# Main.net
KiCad netlist of a schematic drawn in Altium Designer
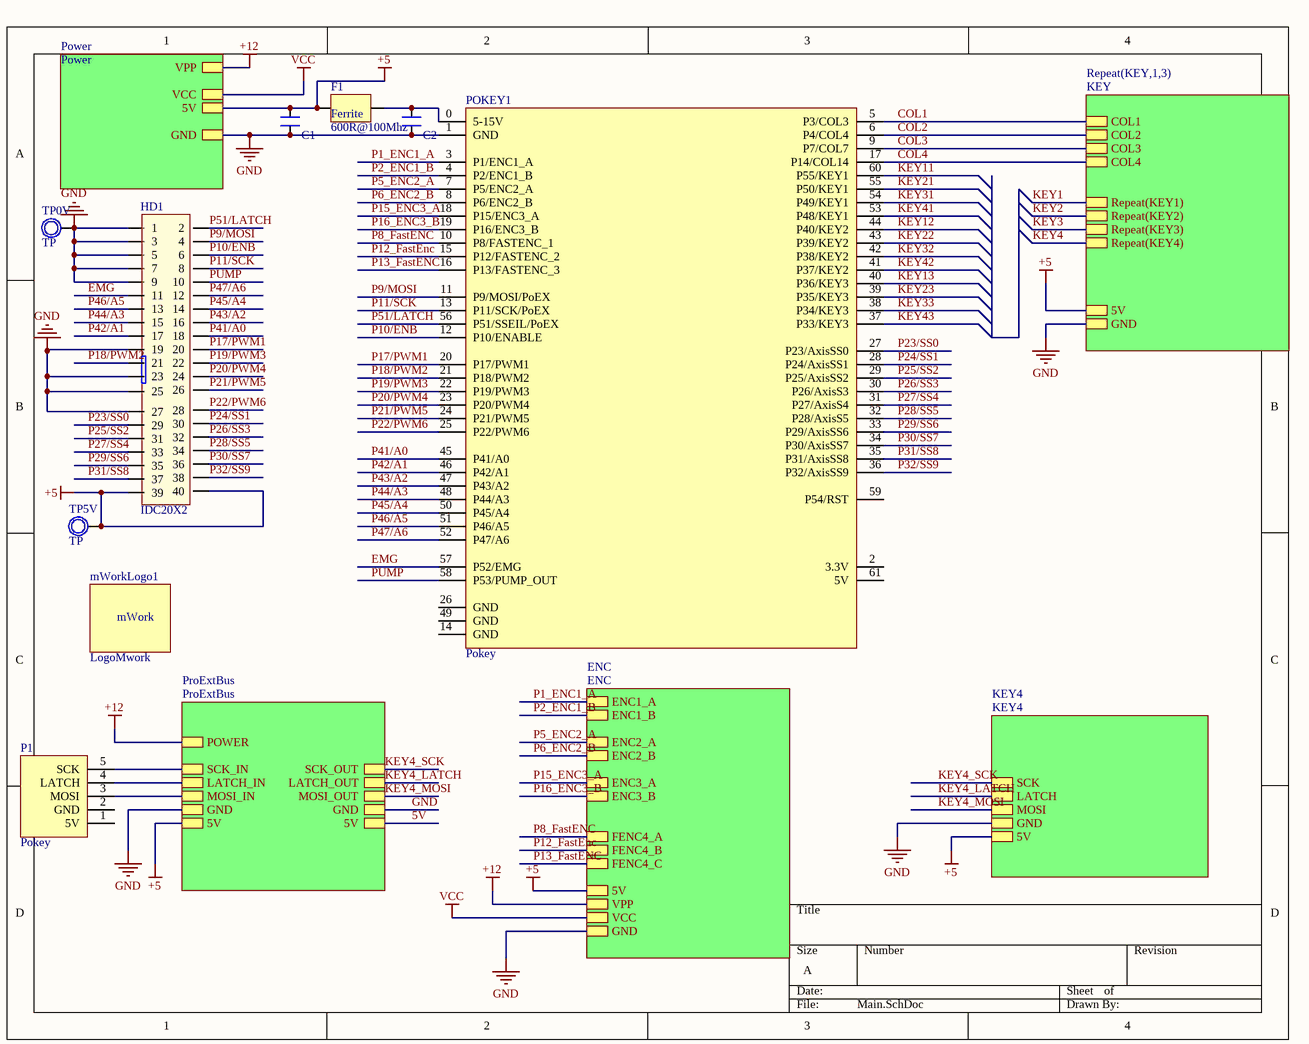
[diagram p0: Main.SchDoc]

(export (version "E")
  (design (tool "Eeschema 10.0.6"))
  (components
    (comp (ref "C1") (value "CN") (footprint "CN-SMD-0603_big") (libsource (lib "nhan") (part "CN")))
    (comp (ref "C2") (value "CN") (footprint "CN-SMD-0603_big") (libsource (lib "nhan") (part "CN")))
    (comp (ref "F1")
      (value "600R@100Mhz")
      (footprint "Capacitor_805")
      (libsource (lib "nhan") (part "Ferrite"))
    )
    (comp (ref "HD1")
      (value "IDC20X2")
      (footprint "IDC40")
      (description "IDC 13x2")
      (libsource (lib "nhan") (part "IDC20X2"))
    )
    (comp (ref "mWorkLogo1")
      (value "LogoMwork")
      (footprint "LogoMwork30*12")
      (libsource (lib "nhan") (part "LogoMwork"))
    )
    (comp (ref "P1") (value "Pokey") (footprint "JACK5") (libsource (lib "nhan") (part "Pokey_Jack")))
    (comp (ref "POKEY1") (value "Pokey") (footprint "POKEY") (libsource (lib "nhan") (part "Pokey")))
    (comp (ref "TP0V")
      (value "TP")
      (footprint "TP1")
      (description "Test Point")
      (libsource (lib "syhaunguyen") (part "TP1"))
    )
    (comp (ref "TP5V")
      (value "TP")
      (footprint "TP1")
      (description "Test Point")
      (libsource (lib "syhaunguyen") (part "TP1"))
    )
  )
  (nets
    (net (code "1") (name "+5") (class "Default")
      (node (ref "C1") (pin "2") (pinfunction "2_2") (pintype "passive"))
      (node (ref "F1") (pin "1") (pinfunction "1_1") (pintype "passive"))
      (node (ref "HD1") (pin "39") (pinfunction "39_39") (pintype "passive"))
      (node (ref "HD1") (pin "40") (pinfunction "40_40") (pintype "passive"))
      (node (ref "TP5V") (pin "1") (pinfunction "1_1") (pintype "passive"))
    )
    (net (code "4") (name "/COL1") (class "Default")
      (node (ref "POKEY1") (pin "5") (pinfunction "P3/COL3_5") (pintype "passive"))
    )
    (net (code "5") (name "/COL2") (class "Default")
      (node (ref "POKEY1") (pin "6") (pinfunction "P4/COL4_6") (pintype "passive"))
    )
    (net (code "6") (name "/COL3") (class "Default")
      (node (ref "POKEY1") (pin "9") (pinfunction "P7/COL7_9") (pintype "passive"))
    )
    (net (code "7") (name "/COL4") (class "Default")
      (node (ref "POKEY1") (pin "17") (pinfunction "P14/COL14_17") (pintype "passive"))
    )
    (net (code "8") (name "/EMG") (class "Default")
      (node (ref "HD1") (pin "11") (pinfunction "11_11") (pintype "passive"))
      (node (ref "POKEY1") (pin "57") (pinfunction "P52/EMG_57") (pintype "passive"))
    )
    (net (code "16") (name "/KEY11") (class "Default")
      (node (ref "POKEY1") (pin "60") (pinfunction "P55/KEY1_60") (pintype "passive"))
    )
    (net (code "17") (name "/KEY12") (class "Default")
      (node (ref "POKEY1") (pin "44") (pinfunction "P40/KEY2_44") (pintype "passive"))
    )
    (net (code "18") (name "/KEY13") (class "Default")
      (node (ref "POKEY1") (pin "40") (pinfunction "P36/KEY3_40") (pintype "passive"))
    )
    (net (code "19") (name "/KEY21") (class "Default")
      (node (ref "POKEY1") (pin "55") (pinfunction "P50/KEY1_55") (pintype "passive"))
    )
    (net (code "20") (name "/KEY22") (class "Default")
      (node (ref "POKEY1") (pin "43") (pinfunction "P39/KEY2_43") (pintype "passive"))
    )
    (net (code "21") (name "/KEY23") (class "Default")
      (node (ref "POKEY1") (pin "39") (pinfunction "P35/KEY3_39") (pintype "passive"))
    )
    (net (code "22") (name "/KEY31") (class "Default")
      (node (ref "POKEY1") (pin "54") (pinfunction "P49/KEY1_54") (pintype "passive"))
    )
    (net (code "23") (name "/KEY32") (class "Default")
      (node (ref "POKEY1") (pin "42") (pinfunction "P38/KEY2_42") (pintype "passive"))
    )
    (net (code "24") (name "/KEY33") (class "Default")
      (node (ref "POKEY1") (pin "38") (pinfunction "P34/KEY3_38") (pintype "passive"))
    )
    (net (code "25") (name "/KEY41") (class "Default")
      (node (ref "POKEY1") (pin "53") (pinfunction "P48/KEY1_53") (pintype "passive"))
    )
    (net (code "26") (name "/KEY42") (class "Default")
      (node (ref "POKEY1") (pin "41") (pinfunction "P37/KEY2_41") (pintype "passive"))
    )
    (net (code "27") (name "/KEY43") (class "Default")
      (node (ref "POKEY1") (pin "37") (pinfunction "P33/KEY3_37") (pintype "passive"))
    )
    (net (code "28") (name "/LATCH_IN") (class "Default")
      (node (ref "P1") (pin "4") (pinfunction "LATCH_4") (pintype "passive"))
    )
    (net (code "29") (name "/MOSI_IN") (class "Default")
      (node (ref "P1") (pin "3") (pinfunction "MOSI_3") (pintype "passive"))
    )
    (net (code "30") (name "/P1_ENC1_A") (class "Default")
      (node (ref "POKEY1") (pin "3") (pinfunction "P1/ENC1_A_3") (pintype "passive"))
    )
    (net (code "31") (name "/P2_ENC1_B") (class "Default")
      (node (ref "POKEY1") (pin "4") (pinfunction "P2/ENC1_B_4") (pintype "passive"))
    )
    (net (code "32") (name "/P5_ENC2_A") (class "Default")
      (node (ref "POKEY1") (pin "7") (pinfunction "P5/ENC2_A_7") (pintype "passive"))
    )
    (net (code "33") (name "/P6_ENC2_B") (class "Default")
      (node (ref "POKEY1") (pin "8") (pinfunction "P6/ENC2_B_8") (pintype "passive"))
    )
    (net (code "34") (name "/P8_FastENC") (class "Default")
      (node (ref "POKEY1") (pin "10") (pinfunction "P8/FASTENC_1_10") (pintype "passive"))
    )
    (net (code "35") (name "/P9{slash}MOSI") (class "Default")
      (node (ref "HD1") (pin "4") (pinfunction "4_4") (pintype "passive"))
      (node (ref "POKEY1") (pin "11") (pinfunction "P9/MOSI/PoEX_11") (pintype "passive"))
    )
    (net (code "36") (name "/P10{slash}ENB") (class "Default")
      (node (ref "HD1") (pin "6") (pinfunction "6_6") (pintype "passive"))
      (node (ref "POKEY1") (pin "12") (pinfunction "P10/ENABLE_12") (pintype "passive"))
    )
    (net (code "37") (name "/P11{slash}SCK") (class "Default")
      (node (ref "HD1") (pin "8") (pinfunction "8_8") (pintype "passive"))
      (node (ref "POKEY1") (pin "13") (pinfunction "P11/SCK/PoEX_13") (pintype "passive"))
    )
    (net (code "38") (name "/P12_FastEnc") (class "Default")
      (node (ref "POKEY1") (pin "15") (pinfunction "P12/FASTENC_2_15") (pintype "passive"))
    )
    (net (code "39") (name "/P13_FastENC") (class "Default")
      (node (ref "POKEY1") (pin "16") (pinfunction "P13/FASTENC_3_16") (pintype "passive"))
    )
    (net (code "40") (name "/P15_ENC3_A") (class "Default")
      (node (ref "POKEY1") (pin "18") (pinfunction "P15/ENC3_A_18") (pintype "passive"))
    )
    (net (code "41") (name "/P16_ENC3_B") (class "Default")
      (node (ref "POKEY1") (pin "19") (pinfunction "P16/ENC3_B_19") (pintype "passive"))
    )
    (net (code "42") (name "/P17{slash}PWM1") (class "Default")
      (node (ref "HD1") (pin "20") (pinfunction "20_20") (pintype "passive"))
      (node (ref "POKEY1") (pin "20") (pinfunction "P17/PWM1_20") (pintype "passive"))
    )
    (net (code "43") (name "/P18{slash}PWM2") (class "Default")
      (node (ref "HD1") (pin "21") (pinfunction "21_21") (pintype "passive"))
      (node (ref "POKEY1") (pin "21") (pinfunction "P18/PWM2_21") (pintype "passive"))
    )
    (net (code "44") (name "/P19{slash}PWM3") (class "Default")
      (node (ref "HD1") (pin "22") (pinfunction "22_22") (pintype "passive"))
      (node (ref "POKEY1") (pin "22") (pinfunction "P19/PWM3_22") (pintype "passive"))
    )
    (net (code "45") (name "/P20{slash}PWM4") (class "Default")
      (node (ref "HD1") (pin "24") (pinfunction "24_24") (pintype "passive"))
      (node (ref "POKEY1") (pin "23") (pinfunction "P20/PWM4_23") (pintype "passive"))
    )
    (net (code "46") (name "/P21{slash}PWM5") (class "Default")
      (node (ref "HD1") (pin "26") (pinfunction "26_26") (pintype "passive"))
      (node (ref "POKEY1") (pin "24") (pinfunction "P21/PWM5_24") (pintype "passive"))
    )
    (net (code "47") (name "/P22{slash}PWM6") (class "Default")
      (node (ref "HD1") (pin "28") (pinfunction "28_28") (pintype "passive"))
      (node (ref "POKEY1") (pin "25") (pinfunction "P22/PWM6_25") (pintype "passive"))
    )
    (net (code "48") (name "/P23{slash}SS0") (class "Default")
      (node (ref "HD1") (pin "29") (pinfunction "29_29") (pintype "passive"))
      (node (ref "POKEY1") (pin "27") (pinfunction "P23/AxisSS0_27") (pintype "passive"))
    )
    (net (code "49") (name "/P24{slash}SS1") (class "Default")
      (node (ref "HD1") (pin "30") (pinfunction "30_30") (pintype "passive"))
      (node (ref "POKEY1") (pin "28") (pinfunction "P24/AxisSS1_28") (pintype "passive"))
    )
    (net (code "50") (name "/P25{slash}SS2") (class "Default")
      (node (ref "HD1") (pin "31") (pinfunction "31_31") (pintype "passive"))
      (node (ref "POKEY1") (pin "29") (pinfunction "P25/AxisSS2_29") (pintype "passive"))
    )
    (net (code "51") (name "/P26{slash}SS3") (class "Default")
      (node (ref "HD1") (pin "32") (pinfunction "32_32") (pintype "passive"))
      (node (ref "POKEY1") (pin "30") (pinfunction "P26/AxisS3_30") (pintype "passive"))
    )
    (net (code "52") (name "/P27{slash}SS4") (class "Default")
      (node (ref "HD1") (pin "33") (pinfunction "33_33") (pintype "passive"))
      (node (ref "POKEY1") (pin "31") (pinfunction "P27/AxisS4_31") (pintype "passive"))
    )
    (net (code "53") (name "/P28{slash}SS5") (class "Default")
      (node (ref "HD1") (pin "34") (pinfunction "34_34") (pintype "passive"))
      (node (ref "POKEY1") (pin "32") (pinfunction "P28/AxisS5_32") (pintype "passive"))
    )
    (net (code "54") (name "/P29{slash}SS6") (class "Default")
      (node (ref "HD1") (pin "35") (pinfunction "35_35") (pintype "passive"))
      (node (ref "POKEY1") (pin "33") (pinfunction "P29/AxisSS6_33") (pintype "passive"))
    )
    (net (code "55") (name "/P30{slash}SS7") (class "Default")
      (node (ref "HD1") (pin "36") (pinfunction "36_36") (pintype "passive"))
      (node (ref "POKEY1") (pin "34") (pinfunction "P30/AxisSS7_34") (pintype "passive"))
    )
    (net (code "56") (name "/P31{slash}SS8") (class "Default")
      (node (ref "HD1") (pin "37") (pinfunction "37_37") (pintype "passive"))
      (node (ref "POKEY1") (pin "35") (pinfunction "P31/AxisSS8_35") (pintype "passive"))
    )
    (net (code "57") (name "/P32{slash}SS9") (class "Default")
      (node (ref "HD1") (pin "38") (pinfunction "38_38") (pintype "passive"))
      (node (ref "POKEY1") (pin "36") (pinfunction "P32/AxisSS9_36") (pintype "passive"))
    )
    (net (code "58") (name "/P41{slash}A0") (class "Default")
      (node (ref "HD1") (pin "18") (pinfunction "18_18") (pintype "passive"))
      (node (ref "POKEY1") (pin "45") (pinfunction "P41/A0_45") (pintype "passive"))
    )
    (net (code "59") (name "/P42{slash}A1") (class "Default")
      (node (ref "HD1") (pin "17") (pinfunction "17_17") (pintype "passive"))
      (node (ref "POKEY1") (pin "46") (pinfunction "P42/A1_46") (pintype "passive"))
    )
    (net (code "60") (name "/P43{slash}A2") (class "Default")
      (node (ref "HD1") (pin "16") (pinfunction "16_16") (pintype "passive"))
      (node (ref "POKEY1") (pin "47") (pinfunction "P43/A2_47") (pintype "passive"))
    )
    (net (code "61") (name "/P44{slash}A3") (class "Default")
      (node (ref "HD1") (pin "15") (pinfunction "15_15") (pintype "passive"))
      (node (ref "POKEY1") (pin "48") (pinfunction "P44/A3_48") (pintype "passive"))
    )
    (net (code "62") (name "/P45{slash}A4") (class "Default")
      (node (ref "HD1") (pin "14") (pinfunction "14_14") (pintype "passive"))
      (node (ref "POKEY1") (pin "50") (pinfunction "P45/A4_50") (pintype "passive"))
    )
    (net (code "63") (name "/P46{slash}A5") (class "Default")
      (node (ref "HD1") (pin "13") (pinfunction "13_13") (pintype "passive"))
      (node (ref "POKEY1") (pin "51") (pinfunction "P46/A5_51") (pintype "passive"))
    )
    (net (code "64") (name "/P47{slash}A6") (class "Default")
      (node (ref "HD1") (pin "12") (pinfunction "12_12") (pintype "passive"))
      (node (ref "POKEY1") (pin "52") (pinfunction "P47/A6_52") (pintype "passive"))
    )
    (net (code "65") (name "/P51{slash}LATCH") (class "Default")
      (node (ref "HD1") (pin "2") (pinfunction "2_2") (pintype "passive"))
      (node (ref "POKEY1") (pin "56") (pinfunction "P51/SSEIL/PoEX_56") (pintype "passive"))
    )
    (net (code "66") (name "/PUMP") (class "Default")
      (node (ref "HD1") (pin "10") (pinfunction "10_10") (pintype "passive"))
      (node (ref "POKEY1") (pin "58") (pinfunction "P53/PUMP_OUT_58") (pintype "passive"))
    )
    (net (code "67") (name "/SCK_IN") (class "Default")
      (node (ref "P1") (pin "5") (pinfunction "SCK_5") (pintype "passive"))
    )
    (net (code "68") (name "GND") (class "Default")
      (node (ref "C1") (pin "1") (pinfunction "1_1") (pintype "passive"))
      (node (ref "C2") (pin "1") (pinfunction "1_1") (pintype "passive"))
      (node (ref "HD1") (pin "1") (pinfunction "1_1") (pintype "passive"))
      (node (ref "HD1") (pin "19") (pinfunction "19_19") (pintype "passive"))
      (node (ref "HD1") (pin "23") (pinfunction "23_23") (pintype "passive"))
      (node (ref "HD1") (pin "25") (pinfunction "25_25") (pintype "passive"))
      (node (ref "HD1") (pin "27") (pinfunction "27_27") (pintype "passive"))
      (node (ref "HD1") (pin "3") (pinfunction "3_3") (pintype "passive"))
      (node (ref "HD1") (pin "5") (pinfunction "5_5") (pintype "passive"))
      (node (ref "HD1") (pin "7") (pinfunction "7_7") (pintype "passive"))
      (node (ref "HD1") (pin "9") (pinfunction "9_9") (pintype "passive"))
      (node (ref "POKEY1") (pin "1") (pinfunction "GND_1") (pintype "passive"))
      (node (ref "TP0V") (pin "1") (pinfunction "1_1") (pintype "passive"))
    )
    (net (code "69") (name "Net-(POKEY1-5-15V)") (class "Default")
      (node (ref "C2") (pin "2") (pinfunction "2_2") (pintype "passive"))
      (node (ref "F1") (pin "2") (pinfunction "2_2") (pintype "passive"))
      (node (ref "POKEY1") (pin "0") (pinfunction "5-15V_0") (pintype "passive"))
    )
    (net (code "71") (name "unconnected-(P1-5V-Pad1)") (class "Default")
      (node (ref "P1") (pin "1") (pinfunction "5V_1") (pintype "passive"))
    )
    (net (code "72") (name "unconnected-(P1-GND-Pad2)") (class "Default")
      (node (ref "P1") (pin "2") (pinfunction "GND_2") (pintype "passive"))
    )
    (net (code "73") (name "unconnected-(POKEY1-3.3V-Pad2)") (class "Default")
      (node (ref "POKEY1") (pin "2") (pinfunction "3.3V_2") (pintype "passive"))
    )
    (net (code "74") (name "unconnected-(POKEY1-5V-Pad61)") (class "Default")
      (node (ref "POKEY1") (pin "61") (pinfunction "5V_61") (pintype "passive"))
    )
    (net (code "75") (name "unconnected-(POKEY1-GND-Pad14)") (class "Default")
      (node (ref "POKEY1") (pin "14") (pinfunction "GND_14") (pintype "passive"))
    )
    (net (code "76") (name "unconnected-(POKEY1-GND-Pad26)") (class "Default")
      (node (ref "POKEY1") (pin "26") (pinfunction "GND_26") (pintype "passive"))
    )
    (net (code "77") (name "unconnected-(POKEY1-GND-Pad49)") (class "Default")
      (node (ref "POKEY1") (pin "49") (pinfunction "GND_49") (pintype "passive"))
    )
    (net (code "78") (name "unconnected-(POKEY1-P54{slash}RST-Pad59)") (class "Default")
      (node (ref "POKEY1") (pin "59") (pinfunction "P54/RST_59") (pintype "passive"))
    )
  )
)
